# BigTime45.net
KiCad netlist of a schematic drawn in EAGLE
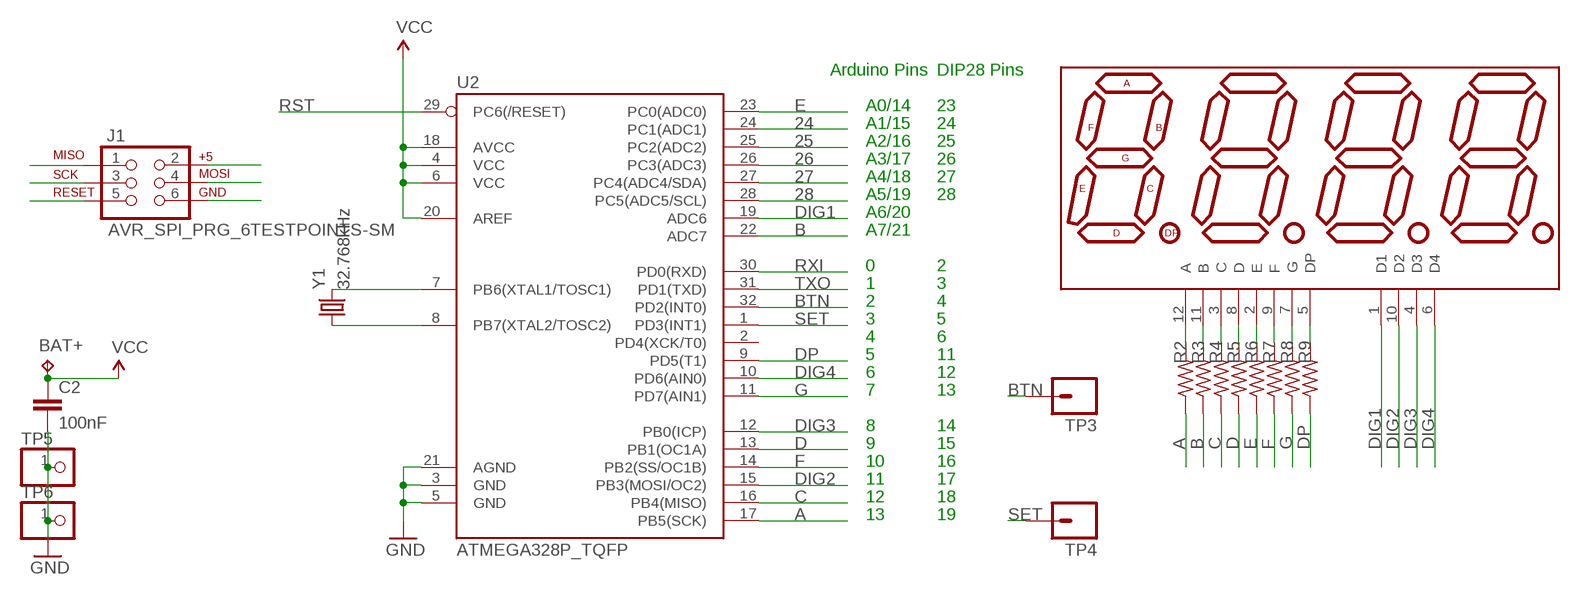
[diagram p0: schematic, sheet 1]

(export (version "E")
  (design (tool "Eeschema 10.0.6"))
  (components
    (comp (ref "BAT+")
      (value "TPTP20R")
      (footprint "eagle-import:TP20R")
      (libsource (lib "eagle-import") (part "TPTP20R"))
    )
    (comp (ref "C2")
      (value "100nF")
      (footprint "eagle-import:C0805")
      (libsource (lib "eagle-import") (part "C-EUC0805"))
    )
    (comp (ref "DISP1")
      (value "7-SEGMENT-4DIGIT-COUNTER-HP-BUBBLE-SM")
      (footprint "eagle-import:DIL12_SM")
      (libsource (lib "eagle-import") (part "7-SEGMENT-4DIGIT-COUNTER-HP-BUBBLE-SM"))
    )
    (comp (ref "J1")
      (value "AVR_SPI_PRG_6TESTPOINTS-SM")
      (footprint "eagle-import:2X3_TEST_POINTS_SM")
      (libsource (lib "eagle-import") (part "AVR_SPI_PRG_6TESTPOINTS-SM"))
    )
    (comp (ref "R2")
      (value "330")
      (footprint "eagle-import:R0805")
      (libsource (lib "eagle-import") (part "R-US_R0805"))
    )
    (comp (ref "R3")
      (value "330")
      (footprint "eagle-import:R0805")
      (libsource (lib "eagle-import") (part "R-US_R0805"))
    )
    (comp (ref "R4")
      (value "330")
      (footprint "eagle-import:R0805")
      (libsource (lib "eagle-import") (part "R-US_R0805"))
    )
    (comp (ref "R5")
      (value "330")
      (footprint "eagle-import:R0805")
      (libsource (lib "eagle-import") (part "R-US_R0805"))
    )
    (comp (ref "R6")
      (value "330")
      (footprint "eagle-import:R0805")
      (libsource (lib "eagle-import") (part "R-US_R0805"))
    )
    (comp (ref "R7")
      (value "330")
      (footprint "eagle-import:R0805")
      (libsource (lib "eagle-import") (part "R-US_R0805"))
    )
    (comp (ref "R8")
      (value "330")
      (footprint "eagle-import:R0805")
      (libsource (lib "eagle-import") (part "R-US_R0805"))
    )
    (comp (ref "R9")
      (value "330")
      (footprint "eagle-import:R0805")
      (libsource (lib "eagle-import") (part "R-US_R0805"))
    )
    (comp (ref "TP3")
      (value "M01EDGE_CONTACT")
      (footprint "eagle-import:WATCHBTN")
      (libsource (lib "eagle-import") (part "M01EDGE_CONTACT"))
    )
    (comp (ref "TP4")
      (value "M01EDGE_CONTACT")
      (footprint "eagle-import:WATCHBTN")
      (libsource (lib "eagle-import") (part "M01EDGE_CONTACT"))
    )
    (comp (ref "TP5")
      (value "PINHD-1X1CB")
      (footprint "eagle-import:1X01-CLEANBIG")
      (libsource (lib "eagle-import") (part "PINHD-1X1CB"))
    )
    (comp (ref "TP6")
      (value "PINHD-1X1CB")
      (footprint "eagle-import:1X01-CLEANBIG")
      (libsource (lib "eagle-import") (part "PINHD-1X1CB"))
    )
    (comp (ref "U2")
      (value "ATMEGA328P_TQFP")
      (footprint "eagle-import:TQFP32-08")
      (libsource (lib "eagle-import") (part "ATMEGA328P_TQFP"))
    )
    (comp (ref "Y1")
      (value "32.768kHz")
      (footprint "eagle-import:TC26H")
      (libsource (lib "eagle-import") (part "CRYSTALTC26H"))
    )
  )
  (nets
    (net (code "1") (name "/24") (class "Default")
      (node (ref "U2") (pin "24") (pinfunction "PC1(ADC1)_24") (pintype "bidirectional"))
    )
    (net (code "2") (name "/25") (class "Default")
      (node (ref "U2") (pin "25") (pinfunction "PC2(ADC2)_25") (pintype "bidirectional"))
    )
    (net (code "3") (name "/26") (class "Default")
      (node (ref "U2") (pin "26") (pinfunction "PC3(ADC3)_26") (pintype "bidirectional"))
    )
    (net (code "4") (name "/27") (class "Default")
      (node (ref "U2") (pin "27") (pinfunction "PC4(ADC4/SDA)_27") (pintype "bidirectional"))
    )
    (net (code "5") (name "/28") (class "Default")
      (node (ref "U2") (pin "28") (pinfunction "PC5(ADC5/SCL)_28") (pintype "bidirectional"))
    )
    (net (code "6") (name "/A") (class "Default")
      (node (ref "J1") (pin "3") (pinfunction "3_3") (pintype "passive"))
      (node (ref "R2") (pin "1") (pinfunction "1_1") (pintype "passive"))
      (node (ref "U2") (pin "17") (pinfunction "PB5(SCK)_17") (pintype "bidirectional"))
    )
    (net (code "7") (name "/B") (class "Default")
      (node (ref "R3") (pin "1") (pinfunction "1_1") (pintype "passive"))
      (node (ref "U2") (pin "22") (pinfunction "ADC7_22") (pintype "bidirectional"))
    )
    (net (code "8") (name "/BTN") (class "Default")
      (node (ref "TP3") (pin "1") (pinfunction "1_1") (pintype "passive"))
      (node (ref "U2") (pin "32") (pinfunction "PD2(INT0)_32") (pintype "bidirectional"))
    )
    (net (code "9") (name "/C") (class "Default")
      (node (ref "J1") (pin "1") (pinfunction "1_1") (pintype "passive"))
      (node (ref "R4") (pin "1") (pinfunction "1_1") (pintype "passive"))
      (node (ref "U2") (pin "16") (pinfunction "PB4(MISO)_16") (pintype "bidirectional"))
    )
    (net (code "10") (name "/D") (class "Default")
      (node (ref "R5") (pin "1") (pinfunction "1_1") (pintype "passive"))
      (node (ref "U2") (pin "13") (pinfunction "PB1(OC1A)_13") (pintype "bidirectional"))
    )
    (net (code "11") (name "/DIG1") (class "Default")
      (node (ref "DISP1") (pin "1") (pinfunction "D1_1") (pintype "bidirectional"))
      (node (ref "U2") (pin "19") (pinfunction "ADC6_19") (pintype "bidirectional"))
    )
    (net (code "12") (name "/DIG2") (class "Default")
      (node (ref "DISP1") (pin "10") (pinfunction "D2_10") (pintype "bidirectional"))
      (node (ref "J1") (pin "4") (pinfunction "4_4") (pintype "passive"))
      (node (ref "U2") (pin "15") (pinfunction "PB3(MOSI/OC2)_15") (pintype "bidirectional"))
    )
    (net (code "13") (name "/DIG3") (class "Default")
      (node (ref "DISP1") (pin "4") (pinfunction "D3_4") (pintype "bidirectional"))
      (node (ref "U2") (pin "12") (pinfunction "PB0(ICP)_12") (pintype "bidirectional"))
    )
    (net (code "14") (name "/DIG4") (class "Default")
      (node (ref "DISP1") (pin "6") (pinfunction "D4_6") (pintype "bidirectional"))
      (node (ref "U2") (pin "10") (pinfunction "PD6(AIN0)_10") (pintype "bidirectional"))
    )
    (net (code "15") (name "/DP") (class "Default")
      (node (ref "R9") (pin "1") (pinfunction "1_1") (pintype "passive"))
      (node (ref "U2") (pin "9") (pinfunction "PD5(T1)_9") (pintype "bidirectional"))
    )
    (net (code "16") (name "/E") (class "Default")
      (node (ref "R6") (pin "1") (pinfunction "1_1") (pintype "passive"))
      (node (ref "U2") (pin "23") (pinfunction "PC0(ADC0)_23") (pintype "bidirectional"))
    )
    (net (code "17") (name "/F") (class "Default")
      (node (ref "R7") (pin "1") (pinfunction "1_1") (pintype "passive"))
      (node (ref "U2") (pin "14") (pinfunction "PB2(SS/OC1B)_14") (pintype "bidirectional"))
    )
    (net (code "18") (name "/G") (class "Default")
      (node (ref "R8") (pin "1") (pinfunction "1_1") (pintype "passive"))
      (node (ref "U2") (pin "11") (pinfunction "PD7(AIN1)_11") (pintype "bidirectional"))
    )
    (net (code "19") (name "/RST") (class "Default")
      (node (ref "J1") (pin "5") (pinfunction "5_5") (pintype "passive"))
      (node (ref "U2") (pin "29") (pinfunction "PC6(/RESET)_29") (pintype "bidirectional"))
    )
    (net (code "20") (name "/RXI") (class "Default")
      (node (ref "U2") (pin "30") (pinfunction "PD0(RXD)_30") (pintype "bidirectional"))
    )
    (net (code "21") (name "/SET") (class "Default")
      (node (ref "TP4") (pin "1") (pinfunction "1_1") (pintype "passive"))
      (node (ref "U2") (pin "1") (pinfunction "PD3(INT1)_1") (pintype "bidirectional"))
    )
    (net (code "22") (name "/TXO") (class "Default")
      (node (ref "U2") (pin "31") (pinfunction "PD1(TXD)_31") (pintype "bidirectional"))
    )
    (net (code "23") (name "GND") (class "Default")
      (node (ref "C2") (pin "2") (pinfunction "2_2") (pintype "passive"))
      (node (ref "J1") (pin "6") (pinfunction "6_6") (pintype "passive"))
      (node (ref "TP5") (pin "1") (pinfunction "1_1") (pintype "passive"))
      (node (ref "TP6") (pin "1") (pinfunction "1_1") (pintype "passive"))
      (node (ref "U2") (pin "21") (pinfunction "AGND_21") (pintype "bidirectional"))
      (node (ref "U2") (pin "3") (pinfunction "GND_3") (pintype "bidirectional"))
      (node (ref "U2") (pin "5") (pinfunction "GND_5") (pintype "bidirectional"))
    )
    (net (code "24") (name "Net-(DISP1-A)") (class "Default")
      (node (ref "DISP1") (pin "12") (pinfunction "A_12") (pintype "bidirectional"))
      (node (ref "R2") (pin "2") (pinfunction "2_2") (pintype "passive"))
    )
    (net (code "25") (name "Net-(DISP1-B)") (class "Default")
      (node (ref "DISP1") (pin "11") (pinfunction "B_11") (pintype "bidirectional"))
      (node (ref "R3") (pin "2") (pinfunction "2_2") (pintype "passive"))
    )
    (net (code "26") (name "Net-(DISP1-C)") (class "Default")
      (node (ref "DISP1") (pin "3") (pinfunction "C_3") (pintype "bidirectional"))
      (node (ref "R4") (pin "2") (pinfunction "2_2") (pintype "passive"))
    )
    (net (code "27") (name "Net-(DISP1-D)") (class "Default")
      (node (ref "DISP1") (pin "8") (pinfunction "D_8") (pintype "bidirectional"))
      (node (ref "R5") (pin "2") (pinfunction "2_2") (pintype "passive"))
    )
    (net (code "28") (name "Net-(DISP1-DP)") (class "Default")
      (node (ref "DISP1") (pin "5") (pinfunction "DP_5") (pintype "bidirectional"))
      (node (ref "R9") (pin "2") (pinfunction "2_2") (pintype "passive"))
    )
    (net (code "29") (name "Net-(DISP1-E)") (class "Default")
      (node (ref "DISP1") (pin "2") (pinfunction "E_2") (pintype "bidirectional"))
      (node (ref "R6") (pin "2") (pinfunction "2_2") (pintype "passive"))
    )
    (net (code "30") (name "Net-(DISP1-F)") (class "Default")
      (node (ref "DISP1") (pin "9") (pinfunction "F_9") (pintype "bidirectional"))
      (node (ref "R7") (pin "2") (pinfunction "2_2") (pintype "passive"))
    )
    (net (code "31") (name "Net-(DISP1-G)") (class "Default")
      (node (ref "DISP1") (pin "7") (pinfunction "G_7") (pintype "bidirectional"))
      (node (ref "R8") (pin "2") (pinfunction "2_2") (pintype "passive"))
    )
    (net (code "32") (name "Net-(U2-PB6(XTAL1{slash}TOSC1))") (class "Default")
      (node (ref "U2") (pin "7") (pinfunction "PB6(XTAL1/TOSC1)_7") (pintype "bidirectional"))
      (node (ref "Y1") (pin "2") (pinfunction "2_2") (pintype "passive"))
    )
    (net (code "33") (name "Net-(U2-PB7(XTAL2{slash}TOSC2))") (class "Default")
      (node (ref "U2") (pin "8") (pinfunction "PB7(XTAL2/TOSC2)_8") (pintype "bidirectional"))
      (node (ref "Y1") (pin "1") (pinfunction "1_1") (pintype "passive"))
    )
    (net (code "34") (name "VCC") (class "Default")
      (node (ref "BAT+") (pin "TP") (pinfunction "TP_TP") (pintype "input"))
      (node (ref "C2") (pin "1") (pinfunction "1_1") (pintype "passive"))
      (node (ref "J1") (pin "2") (pinfunction "2_2") (pintype "passive"))
      (node (ref "U2") (pin "18") (pinfunction "AVCC_18") (pintype "bidirectional"))
      (node (ref "U2") (pin "20") (pinfunction "AREF_20") (pintype "bidirectional"))
      (node (ref "U2") (pin "4") (pinfunction "VCC_4") (pintype "bidirectional"))
      (node (ref "U2") (pin "6") (pinfunction "VCC_6") (pintype "bidirectional"))
    )
    (net (code "35") (name "unconnected-(U2-PD4(XCK{slash}T0)-Pad2)") (class "Default")
      (node (ref "U2") (pin "2") (pinfunction "PD4(XCK/T0)_2") (pintype "bidirectional"))
    )
  )
)
